# GiGaMega_sield_2.net
KiCad netlist of a schematic drawn in EAGLE
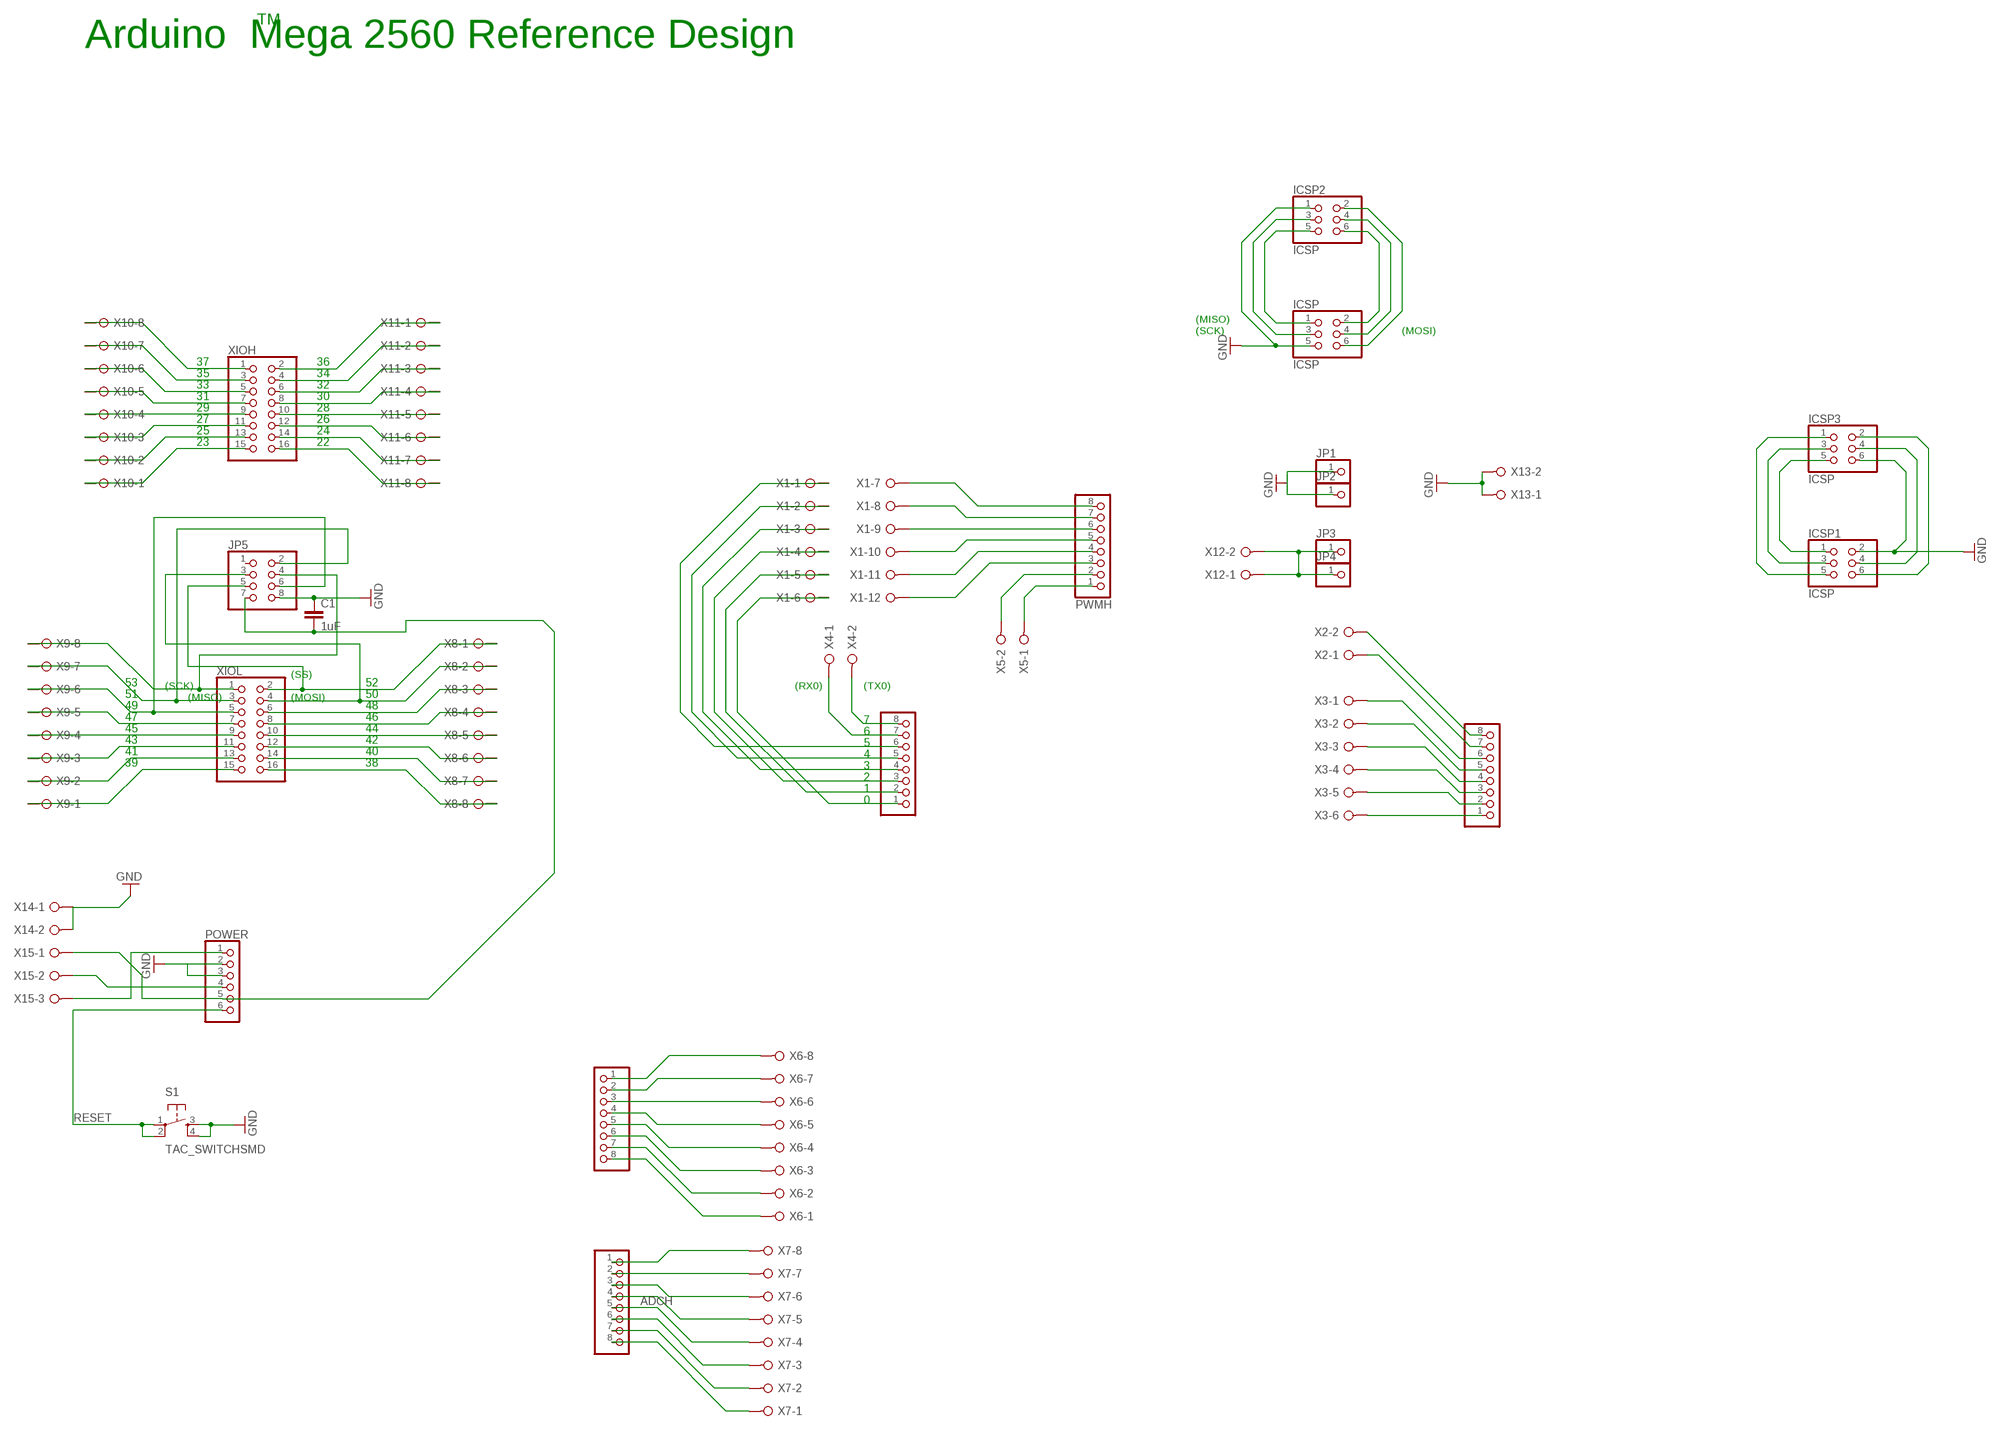
[diagram p0: schematic, sheet 1]

(export (version "E")
  (design (tool "Eeschema 10.0.6"))
  (components
    (comp (ref "ADCH")
      (value "PINHD-1X8")
      (footprint "eagle-import:1X08")
      (libsource (lib "eagle-import") (part "PINHD-1X8"))
    )
    (comp (ref "ADCL")
      (value "PINHD-1X8")
      (footprint "eagle-import:1X08")
      (libsource (lib "eagle-import") (part "PINHD-1X8"))
    )
    (comp (ref "C1")
      (value "1uF")
      (footprint "eagle-import:1206")
      (libsource (lib "eagle-import") (part "2.2UF-CERCAP-10009"))
    )
    (comp (ref "COMMUNICATION")
      (value "PINHD-1X8")
      (footprint "eagle-import:1X08")
      (libsource (lib "eagle-import") (part "PINHD-1X8"))
    )
    (comp (ref "ICSP")
      (value "ICSP")
      (footprint "eagle-import:2X03")
      (libsource (lib "eagle-import") (part "PINHD-2X3"))
    )
    (comp (ref "ICSP1")
      (value "ICSP")
      (footprint "eagle-import:2X03")
      (libsource (lib "eagle-import") (part "PINHD-2X3"))
    )
    (comp (ref "ICSP2")
      (value "ICSP")
      (footprint "eagle-import:2X03")
      (libsource (lib "eagle-import") (part "PINHD-2X3"))
    )
    (comp (ref "ICSP3")
      (value "ICSP")
      (footprint "eagle-import:2X03")
      (libsource (lib "eagle-import") (part "PINHD-2X3"))
    )
    (comp (ref "JP1")
      (value "PINHD-1X1")
      (footprint "eagle-import:1X01")
      (libsource (lib "eagle-import") (part "PINHD-1X1"))
    )
    (comp (ref "JP2")
      (value "PINHD-1X1")
      (footprint "eagle-import:1X01")
      (libsource (lib "eagle-import") (part "PINHD-1X1"))
    )
    (comp (ref "JP3")
      (value "PINHD-1X1")
      (footprint "eagle-import:1X01")
      (libsource (lib "eagle-import") (part "PINHD-1X1"))
    )
    (comp (ref "JP4")
      (value "PINHD-1X1")
      (footprint "eagle-import:1X01")
      (libsource (lib "eagle-import") (part "PINHD-1X1"))
    )
    (comp (ref "JP5")
      (value "PINHD-2X4")
      (footprint "eagle-import:2X04")
      (libsource (lib "eagle-import") (part "PINHD-2X4"))
    )
    (comp (ref "POWER")
      (value "PINHD-1X6")
      (footprint "eagle-import:1X06")
      (libsource (lib "eagle-import") (part "PINHD-1X6"))
    )
    (comp (ref "PWMH")
      (value "PINHD-1X8")
      (footprint "eagle-import:1X08")
      (libsource (lib "eagle-import") (part "PINHD-1X8"))
    )
    (comp (ref "PWML")
      (value "PINHD-1X8")
      (footprint "eagle-import:1X08")
      (libsource (lib "eagle-import") (part "PINHD-1X8"))
    )
    (comp (ref "S1")
      (value "TAC_SWITCHSMD")
      (footprint "eagle-import:TACTILE-SWITCH-SMD")
      (libsource (lib "eagle-import") (part "TAC_SWITCHSMD"))
    )
    (comp (ref "X1")
      (value "W237-12P")
      (footprint "eagle-import:W237-12P")
      (libsource (lib "eagle-import") (part "W237-12P"))
    )
    (comp (ref "X2")
      (value "W237-02P")
      (footprint "eagle-import:W237-132")
      (libsource (lib "eagle-import") (part "W237-02P"))
    )
    (comp (ref "X3")
      (value "W237-06P")
      (footprint "eagle-import:W237-6P")
      (libsource (lib "eagle-import") (part "W237-06P"))
    )
    (comp (ref "X4")
      (value "W237-02P")
      (footprint "eagle-import:W237-132")
      (libsource (lib "eagle-import") (part "W237-02P"))
    )
    (comp (ref "X5")
      (value "W237-02P")
      (footprint "eagle-import:W237-132")
      (libsource (lib "eagle-import") (part "W237-02P"))
    )
    (comp (ref "X6")
      (value "W237-08P")
      (footprint "eagle-import:W237-8P")
      (libsource (lib "eagle-import") (part "W237-08P"))
    )
    (comp (ref "X7")
      (value "W237-08P")
      (footprint "eagle-import:W237-8P")
      (libsource (lib "eagle-import") (part "W237-08P"))
    )
    (comp (ref "X8")
      (value "W237-08P")
      (footprint "eagle-import:W237-8P")
      (libsource (lib "eagle-import") (part "W237-08P"))
    )
    (comp (ref "X9")
      (value "W237-08P")
      (footprint "eagle-import:W237-8P")
      (libsource (lib "eagle-import") (part "W237-08P"))
    )
    (comp (ref "X10")
      (value "W237-08P")
      (footprint "eagle-import:W237-8P")
      (libsource (lib "eagle-import") (part "W237-08P"))
    )
    (comp (ref "X11")
      (value "W237-08P")
      (footprint "eagle-import:W237-8P")
      (libsource (lib "eagle-import") (part "W237-08P"))
    )
    (comp (ref "X12")
      (value "W237-02P")
      (footprint "eagle-import:W237-132")
      (libsource (lib "eagle-import") (part "W237-02P"))
    )
    (comp (ref "X13")
      (value "W237-02P")
      (footprint "eagle-import:W237-132")
      (libsource (lib "eagle-import") (part "W237-02P"))
    )
    (comp (ref "X14")
      (value "W237-02P")
      (footprint "eagle-import:W237-132")
      (libsource (lib "eagle-import") (part "W237-02P"))
    )
    (comp (ref "X15")
      (value "W237-03P")
      (footprint "eagle-import:W237-133")
      (libsource (lib "eagle-import") (part "W237-03P"))
    )
    (comp (ref "XIOH")
      (value "PINHD-2X8")
      (footprint "eagle-import:2X08")
      (libsource (lib "eagle-import") (part "PINHD-2X8"))
    )
    (comp (ref "XIOL")
      (value "PINHD-2X8")
      (footprint "eagle-import:2X08")
      (libsource (lib "eagle-import") (part "PINHD-2X8"))
    )
  )
  (nets
    (net (code "1") (name "/RESET") (class "Default")
      (node (ref "POWER") (pin "6") (pinfunction "6_6") (pintype "passive"))
      (node (ref "S1") (pin "1") (pinfunction "1_1") (pintype "passive"))
      (node (ref "S1") (pin "2") (pinfunction "2_2") (pintype "passive"))
    )
    (net (code "2") (name "GND") (class "Default")
      (node (ref "C1") (pin "1") (pinfunction "1_1") (pintype "passive"))
      (node (ref "ICSP") (pin "5") (pinfunction "5_5") (pintype "passive"))
      (node (ref "ICSP1") (pin "2") (pinfunction "2_2") (pintype "passive"))
      (node (ref "ICSP2") (pin "1") (pinfunction "1_1") (pintype "passive"))
      (node (ref "ICSP3") (pin "6") (pinfunction "6_6") (pintype "passive"))
      (node (ref "JP1") (pin "1") (pinfunction "1_1") (pintype "passive"))
      (node (ref "JP2") (pin "1") (pinfunction "1_1") (pintype "passive"))
      (node (ref "JP5") (pin "8") (pinfunction "8_8") (pintype "passive"))
      (node (ref "POWER") (pin "2") (pinfunction "2_2") (pintype "passive"))
      (node (ref "POWER") (pin "3") (pinfunction "3_3") (pintype "passive"))
      (node (ref "S1") (pin "3") (pinfunction "3_3") (pintype "passive"))
      (node (ref "S1") (pin "4") (pinfunction "4_4") (pintype "passive"))
      (node (ref "X13") (pin "1") (pinfunction "KL_1") (pintype "passive"))
      (node (ref "X13") (pin "2") (pinfunction "KL_2") (pintype "passive"))
      (node (ref "X14") (pin "1") (pinfunction "KL_1") (pintype "passive"))
      (node (ref "X14") (pin "2") (pinfunction "KL_2") (pintype "passive"))
    )
    (net (code "3") (name "Net-(ICSP-Pad1)") (class "Default")
      (node (ref "ICSP") (pin "1") (pinfunction "1_1") (pintype "passive"))
      (node (ref "ICSP2") (pin "5") (pinfunction "5_5") (pintype "passive"))
    )
    (net (code "4") (name "Net-(ICSP-Pad2)") (class "Default")
      (node (ref "ICSP") (pin "2") (pinfunction "2_2") (pintype "passive"))
      (node (ref "ICSP2") (pin "6") (pinfunction "6_6") (pintype "passive"))
    )
    (net (code "5") (name "Net-(ICSP-Pad3)") (class "Default")
      (node (ref "ICSP") (pin "3") (pinfunction "3_3") (pintype "passive"))
      (node (ref "ICSP2") (pin "3") (pinfunction "3_3") (pintype "passive"))
    )
    (net (code "6") (name "Net-(ICSP-Pad4)") (class "Default")
      (node (ref "ICSP") (pin "4") (pinfunction "4_4") (pintype "passive"))
      (node (ref "ICSP2") (pin "4") (pinfunction "4_4") (pintype "passive"))
    )
    (net (code "7") (name "Net-(ICSP-Pad6)") (class "Default")
      (node (ref "ICSP") (pin "6") (pinfunction "6_6") (pintype "passive"))
      (node (ref "ICSP2") (pin "2") (pinfunction "2_2") (pintype "passive"))
    )
    (net (code "8") (name "Net-(ICSP1-Pad1)") (class "Default")
      (node (ref "ICSP1") (pin "1") (pinfunction "1_1") (pintype "passive"))
      (node (ref "ICSP3") (pin "5") (pinfunction "5_5") (pintype "passive"))
    )
    (net (code "9") (name "Net-(ICSP1-Pad3)") (class "Default")
      (node (ref "ICSP1") (pin "3") (pinfunction "3_3") (pintype "passive"))
      (node (ref "ICSP3") (pin "3") (pinfunction "3_3") (pintype "passive"))
    )
    (net (code "10") (name "Net-(ICSP1-Pad4)") (class "Default")
      (node (ref "ICSP1") (pin "4") (pinfunction "4_4") (pintype "passive"))
      (node (ref "ICSP3") (pin "4") (pinfunction "4_4") (pintype "passive"))
    )
    (net (code "11") (name "Net-(ICSP1-Pad5)") (class "Default")
      (node (ref "ICSP1") (pin "5") (pinfunction "5_5") (pintype "passive"))
      (node (ref "ICSP3") (pin "1") (pinfunction "1_1") (pintype "passive"))
    )
    (net (code "12") (name "Net-(ICSP1-Pad6)") (class "Default")
      (node (ref "ICSP1") (pin "6") (pinfunction "6_6") (pintype "passive"))
      (node (ref "ICSP3") (pin "2") (pinfunction "2_2") (pintype "passive"))
    )
    (net (code "13") (name "Net-(X1A-KL)") (class "Default")
      (node (ref "PWML") (pin "6") (pinfunction "6_6") (pintype "passive"))
      (node (ref "X1") (pin "1") (pinfunction "KL_1") (pintype "passive"))
    )
    (net (code "14") (name "Net-(X1B-KL)") (class "Default")
      (node (ref "PWMH") (pin "5") (pinfunction "5_5") (pintype "passive"))
      (node (ref "X1") (pin "10") (pinfunction "KL_10") (pintype "passive"))
    )
    (net (code "15") (name "Net-(X1C-KL)") (class "Default")
      (node (ref "PWMH") (pin "4") (pinfunction "4_4") (pintype "passive"))
      (node (ref "X1") (pin "11") (pinfunction "KL_11") (pintype "passive"))
    )
    (net (code "16") (name "Net-(X1D-KL)") (class "Default")
      (node (ref "PWMH") (pin "3") (pinfunction "3_3") (pintype "passive"))
      (node (ref "X1") (pin "12") (pinfunction "KL_12") (pintype "passive"))
    )
    (net (code "17") (name "Net-(X1E-KL)") (class "Default")
      (node (ref "PWML") (pin "5") (pinfunction "5_5") (pintype "passive"))
      (node (ref "X1") (pin "2") (pinfunction "KL_2") (pintype "passive"))
    )
    (net (code "18") (name "Net-(X1F-KL)") (class "Default")
      (node (ref "PWML") (pin "4") (pinfunction "4_4") (pintype "passive"))
      (node (ref "X1") (pin "3") (pinfunction "KL_3") (pintype "passive"))
    )
    (net (code "19") (name "Net-(X1G-KL)") (class "Default")
      (node (ref "PWML") (pin "3") (pinfunction "3_3") (pintype "passive"))
      (node (ref "X1") (pin "4") (pinfunction "KL_4") (pintype "passive"))
    )
    (net (code "20") (name "Net-(X1H-KL)") (class "Default")
      (node (ref "PWML") (pin "2") (pinfunction "2_2") (pintype "passive"))
      (node (ref "X1") (pin "5") (pinfunction "KL_5") (pintype "passive"))
    )
    (net (code "21") (name "Net-(X1I-KL)") (class "Default")
      (node (ref "PWML") (pin "1") (pinfunction "1_1") (pintype "passive"))
      (node (ref "X1") (pin "6") (pinfunction "KL_6") (pintype "passive"))
    )
    (net (code "22") (name "Net-(X1J-KL)") (class "Default")
      (node (ref "PWMH") (pin "8") (pinfunction "8_8") (pintype "passive"))
      (node (ref "X1") (pin "7") (pinfunction "KL_7") (pintype "passive"))
    )
    (net (code "23") (name "Net-(X1K-KL)") (class "Default")
      (node (ref "PWMH") (pin "7") (pinfunction "7_7") (pintype "passive"))
      (node (ref "X1") (pin "8") (pinfunction "KL_8") (pintype "passive"))
    )
    (net (code "24") (name "Net-(X1L-KL)") (class "Default")
      (node (ref "PWMH") (pin "6") (pinfunction "6_6") (pintype "passive"))
      (node (ref "X1") (pin "9") (pinfunction "KL_9") (pintype "passive"))
    )
    (net (code "25") (name "Net-(X2A-KL)") (class "Default")
      (node (ref "COMMUNICATION") (pin "7") (pinfunction "7_7") (pintype "passive"))
      (node (ref "X2") (pin "1") (pinfunction "KL_1") (pintype "passive"))
    )
    (net (code "26") (name "Net-(X2B-KL)") (class "Default")
      (node (ref "COMMUNICATION") (pin "8") (pinfunction "8_8") (pintype "passive"))
      (node (ref "X2") (pin "2") (pinfunction "KL_2") (pintype "passive"))
    )
    (net (code "27") (name "Net-(X3A-KL)") (class "Default")
      (node (ref "COMMUNICATION") (pin "6") (pinfunction "6_6") (pintype "passive"))
      (node (ref "X3") (pin "1") (pinfunction "KL_1") (pintype "passive"))
    )
    (net (code "28") (name "Net-(X3B-KL)") (class "Default")
      (node (ref "COMMUNICATION") (pin "5") (pinfunction "5_5") (pintype "passive"))
      (node (ref "X3") (pin "2") (pinfunction "KL_2") (pintype "passive"))
    )
    (net (code "29") (name "Net-(X3C-KL)") (class "Default")
      (node (ref "COMMUNICATION") (pin "4") (pinfunction "4_4") (pintype "passive"))
      (node (ref "X3") (pin "3") (pinfunction "KL_3") (pintype "passive"))
    )
    (net (code "30") (name "Net-(X3D-KL)") (class "Default")
      (node (ref "COMMUNICATION") (pin "3") (pinfunction "3_3") (pintype "passive"))
      (node (ref "X3") (pin "4") (pinfunction "KL_4") (pintype "passive"))
    )
    (net (code "31") (name "Net-(X3E-KL)") (class "Default")
      (node (ref "COMMUNICATION") (pin "2") (pinfunction "2_2") (pintype "passive"))
      (node (ref "X3") (pin "5") (pinfunction "KL_5") (pintype "passive"))
    )
    (net (code "32") (name "Net-(X3F-KL)") (class "Default")
      (node (ref "COMMUNICATION") (pin "1") (pinfunction "1_1") (pintype "passive"))
      (node (ref "X3") (pin "6") (pinfunction "KL_6") (pintype "passive"))
    )
    (net (code "33") (name "Net-(X4A-KL)") (class "Default")
      (node (ref "PWML") (pin "7") (pinfunction "7_7") (pintype "passive"))
      (node (ref "X4") (pin "1") (pinfunction "KL_1") (pintype "passive"))
    )
    (net (code "34") (name "Net-(X4B-KL)") (class "Default")
      (node (ref "PWML") (pin "8") (pinfunction "8_8") (pintype "passive"))
      (node (ref "X4") (pin "2") (pinfunction "KL_2") (pintype "passive"))
    )
    (net (code "35") (name "Net-(X5A-KL)") (class "Default")
      (node (ref "PWMH") (pin "1") (pinfunction "1_1") (pintype "passive"))
      (node (ref "X5") (pin "1") (pinfunction "KL_1") (pintype "passive"))
    )
    (net (code "36") (name "Net-(X5B-KL)") (class "Default")
      (node (ref "PWMH") (pin "2") (pinfunction "2_2") (pintype "passive"))
      (node (ref "X5") (pin "2") (pinfunction "KL_2") (pintype "passive"))
    )
    (net (code "37") (name "Net-(X6A-KL)") (class "Default")
      (node (ref "ADCL") (pin "8") (pinfunction "8_8") (pintype "passive"))
      (node (ref "X6") (pin "1") (pinfunction "KL_1") (pintype "passive"))
    )
    (net (code "38") (name "Net-(X6B-KL)") (class "Default")
      (node (ref "ADCL") (pin "7") (pinfunction "7_7") (pintype "passive"))
      (node (ref "X6") (pin "2") (pinfunction "KL_2") (pintype "passive"))
    )
    (net (code "39") (name "Net-(X6C-KL)") (class "Default")
      (node (ref "ADCL") (pin "6") (pinfunction "6_6") (pintype "passive"))
      (node (ref "X6") (pin "3") (pinfunction "KL_3") (pintype "passive"))
    )
    (net (code "40") (name "Net-(X6D-KL)") (class "Default")
      (node (ref "ADCL") (pin "5") (pinfunction "5_5") (pintype "passive"))
      (node (ref "X6") (pin "4") (pinfunction "KL_4") (pintype "passive"))
    )
    (net (code "41") (name "Net-(X6E-KL)") (class "Default")
      (node (ref "ADCL") (pin "4") (pinfunction "4_4") (pintype "passive"))
      (node (ref "X6") (pin "5") (pinfunction "KL_5") (pintype "passive"))
    )
    (net (code "42") (name "Net-(X6F-KL)") (class "Default")
      (node (ref "ADCL") (pin "3") (pinfunction "3_3") (pintype "passive"))
      (node (ref "X6") (pin "6") (pinfunction "KL_6") (pintype "passive"))
    )
    (net (code "43") (name "Net-(X6G-KL)") (class "Default")
      (node (ref "ADCL") (pin "2") (pinfunction "2_2") (pintype "passive"))
      (node (ref "X6") (pin "7") (pinfunction "KL_7") (pintype "passive"))
    )
    (net (code "44") (name "Net-(X6H-KL)") (class "Default")
      (node (ref "ADCL") (pin "1") (pinfunction "1_1") (pintype "passive"))
      (node (ref "X6") (pin "8") (pinfunction "KL_8") (pintype "passive"))
    )
    (net (code "45") (name "Net-(X7A-KL)") (class "Default")
      (node (ref "ADCH") (pin "8") (pinfunction "8_8") (pintype "passive"))
      (node (ref "X7") (pin "1") (pinfunction "KL_1") (pintype "passive"))
    )
    (net (code "46") (name "Net-(X7B-KL)") (class "Default")
      (node (ref "ADCH") (pin "7") (pinfunction "7_7") (pintype "passive"))
      (node (ref "X7") (pin "2") (pinfunction "KL_2") (pintype "passive"))
    )
    (net (code "47") (name "Net-(X7C-KL)") (class "Default")
      (node (ref "ADCH") (pin "6") (pinfunction "6_6") (pintype "passive"))
      (node (ref "X7") (pin "3") (pinfunction "KL_3") (pintype "passive"))
    )
    (net (code "48") (name "Net-(X7D-KL)") (class "Default")
      (node (ref "ADCH") (pin "5") (pinfunction "5_5") (pintype "passive"))
      (node (ref "X7") (pin "4") (pinfunction "KL_4") (pintype "passive"))
    )
    (net (code "49") (name "Net-(X7E-KL)") (class "Default")
      (node (ref "ADCH") (pin "4") (pinfunction "4_4") (pintype "passive"))
      (node (ref "X7") (pin "5") (pinfunction "KL_5") (pintype "passive"))
    )
    (net (code "50") (name "Net-(X7F-KL)") (class "Default")
      (node (ref "ADCH") (pin "3") (pinfunction "3_3") (pintype "passive"))
      (node (ref "X7") (pin "6") (pinfunction "KL_6") (pintype "passive"))
    )
    (net (code "51") (name "Net-(X7G-KL)") (class "Default")
      (node (ref "ADCH") (pin "2") (pinfunction "2_2") (pintype "passive"))
      (node (ref "X7") (pin "7") (pinfunction "KL_7") (pintype "passive"))
    )
    (net (code "52") (name "Net-(X7H-KL)") (class "Default")
      (node (ref "ADCH") (pin "1") (pinfunction "1_1") (pintype "passive"))
      (node (ref "X7") (pin "8") (pinfunction "KL_8") (pintype "passive"))
    )
    (net (code "53") (name "Net-(X8A-KL)") (class "Default")
      (node (ref "JP5") (pin "5") (pinfunction "5_5") (pintype "passive"))
      (node (ref "X8") (pin "1") (pinfunction "KL_1") (pintype "passive"))
      (node (ref "XIOL") (pin "2") (pinfunction "2_2") (pintype "passive"))
    )
    (net (code "54") (name "Net-(X8B-KL)") (class "Default")
      (node (ref "JP5") (pin "3") (pinfunction "3_3") (pintype "passive"))
      (node (ref "X8") (pin "2") (pinfunction "KL_2") (pintype "passive"))
      (node (ref "XIOL") (pin "4") (pinfunction "4_4") (pintype "passive"))
    )
    (net (code "55") (name "Net-(X8C-KL)") (class "Default")
      (node (ref "X8") (pin "3") (pinfunction "KL_3") (pintype "passive"))
      (node (ref "XIOL") (pin "6") (pinfunction "6_6") (pintype "passive"))
    )
    (net (code "56") (name "Net-(X8D-KL)") (class "Default")
      (node (ref "X8") (pin "4") (pinfunction "KL_4") (pintype "passive"))
      (node (ref "XIOL") (pin "8") (pinfunction "8_8") (pintype "passive"))
    )
    (net (code "57") (name "Net-(X8E-KL)") (class "Default")
      (node (ref "X8") (pin "5") (pinfunction "KL_5") (pintype "passive"))
      (node (ref "XIOL") (pin "10") (pinfunction "10_10") (pintype "passive"))
    )
    (net (code "58") (name "Net-(X8F-KL)") (class "Default")
      (node (ref "X8") (pin "6") (pinfunction "KL_6") (pintype "passive"))
      (node (ref "XIOL") (pin "12") (pinfunction "12_12") (pintype "passive"))
    )
    (net (code "59") (name "Net-(X8G-KL)") (class "Default")
      (node (ref "X8") (pin "7") (pinfunction "KL_7") (pintype "passive"))
      (node (ref "XIOL") (pin "14") (pinfunction "14_14") (pintype "passive"))
    )
    (net (code "60") (name "Net-(X8H-KL)") (class "Default")
      (node (ref "X8") (pin "8") (pinfunction "KL_8") (pintype "passive"))
      (node (ref "XIOL") (pin "16") (pinfunction "16_16") (pintype "passive"))
    )
    (net (code "61") (name "Net-(X9A-KL)") (class "Default")
      (node (ref "X9") (pin "1") (pinfunction "KL_1") (pintype "passive"))
      (node (ref "XIOL") (pin "15") (pinfunction "15_15") (pintype "passive"))
    )
    (net (code "62") (name "Net-(X9B-KL)") (class "Default")
      (node (ref "X9") (pin "2") (pinfunction "KL_2") (pintype "passive"))
      (node (ref "XIOL") (pin "13") (pinfunction "13_13") (pintype "passive"))
    )
    (net (code "63") (name "Net-(X9C-KL)") (class "Default")
      (node (ref "X9") (pin "3") (pinfunction "KL_3") (pintype "passive"))
      (node (ref "XIOL") (pin "11") (pinfunction "11_11") (pintype "passive"))
    )
    (net (code "64") (name "Net-(X9D-KL)") (class "Default")
      (node (ref "X9") (pin "4") (pinfunction "KL_4") (pintype "passive"))
      (node (ref "XIOL") (pin "9") (pinfunction "9_9") (pintype "passive"))
    )
    (net (code "65") (name "Net-(X9E-KL)") (class "Default")
      (node (ref "X9") (pin "5") (pinfunction "KL_5") (pintype "passive"))
      (node (ref "XIOL") (pin "7") (pinfunction "7_7") (pintype "passive"))
    )
    (net (code "66") (name "Net-(X9F-KL)") (class "Default")
      (node (ref "JP5") (pin "6") (pinfunction "6_6") (pintype "passive"))
      (node (ref "X9") (pin "6") (pinfunction "KL_6") (pintype "passive"))
      (node (ref "XIOL") (pin "5") (pinfunction "5_5") (pintype "passive"))
    )
    (net (code "67") (name "Net-(X9G-KL)") (class "Default")
      (node (ref "JP5") (pin "2") (pinfunction "2_2") (pintype "passive"))
      (node (ref "X9") (pin "7") (pinfunction "KL_7") (pintype "passive"))
      (node (ref "XIOL") (pin "3") (pinfunction "3_3") (pintype "passive"))
    )
    (net (code "68") (name "Net-(X9H-KL)") (class "Default")
      (node (ref "JP5") (pin "4") (pinfunction "4_4") (pintype "passive"))
      (node (ref "X9") (pin "8") (pinfunction "KL_8") (pintype "passive"))
      (node (ref "XIOL") (pin "1") (pinfunction "1_1") (pintype "passive"))
    )
    (net (code "69") (name "Net-(X10A-KL)") (class "Default")
      (node (ref "X10") (pin "1") (pinfunction "KL_1") (pintype "passive"))
      (node (ref "XIOH") (pin "15") (pinfunction "15_15") (pintype "passive"))
    )
    (net (code "70") (name "Net-(X10B-KL)") (class "Default")
      (node (ref "X10") (pin "2") (pinfunction "KL_2") (pintype "passive"))
      (node (ref "XIOH") (pin "13") (pinfunction "13_13") (pintype "passive"))
    )
    (net (code "71") (name "Net-(X10C-KL)") (class "Default")
      (node (ref "X10") (pin "3") (pinfunction "KL_3") (pintype "passive"))
      (node (ref "XIOH") (pin "11") (pinfunction "11_11") (pintype "passive"))
    )
    (net (code "72") (name "Net-(X10D-KL)") (class "Default")
      (node (ref "X10") (pin "4") (pinfunction "KL_4") (pintype "passive"))
      (node (ref "XIOH") (pin "9") (pinfunction "9_9") (pintype "passive"))
    )
    (net (code "73") (name "Net-(X10E-KL)") (class "Default")
      (node (ref "X10") (pin "5") (pinfunction "KL_5") (pintype "passive"))
      (node (ref "XIOH") (pin "7") (pinfunction "7_7") (pintype "passive"))
    )
    (net (code "74") (name "Net-(X10F-KL)") (class "Default")
      (node (ref "X10") (pin "6") (pinfunction "KL_6") (pintype "passive"))
      (node (ref "XIOH") (pin "5") (pinfunction "5_5") (pintype "passive"))
    )
    (net (code "75") (name "Net-(X10G-KL)") (class "Default")
      (node (ref "X10") (pin "7") (pinfunction "KL_7") (pintype "passive"))
      (node (ref "XIOH") (pin "3") (pinfunction "3_3") (pintype "passive"))
    )
    (net (code "76") (name "Net-(X10H-KL)") (class "Default")
      (node (ref "X10") (pin "8") (pinfunction "KL_8") (pintype "passive"))
      (node (ref "XIOH") (pin "1") (pinfunction "1_1") (pintype "passive"))
    )
    (net (code "77") (name "Net-(X11A-KL)") (class "Default")
      (node (ref "X11") (pin "1") (pinfunction "KL_1") (pintype "passive"))
      (node (ref "XIOH") (pin "2") (pinfunction "2_2") (pintype "passive"))
    )
    (net (code "78") (name "Net-(X11B-KL)") (class "Default")
      (node (ref "X11") (pin "2") (pinfunction "KL_2") (pintype "passive"))
      (node (ref "XIOH") (pin "4") (pinfunction "4_4") (pintype "passive"))
    )
    (net (code "79") (name "Net-(X11C-KL)") (class "Default")
      (node (ref "X11") (pin "3") (pinfunction "KL_3") (pintype "passive"))
      (node (ref "XIOH") (pin "6") (pinfunction "6_6") (pintype "passive"))
    )
    (net (code "80") (name "Net-(X11D-KL)") (class "Default")
      (node (ref "X11") (pin "4") (pinfunction "KL_4") (pintype "passive"))
      (node (ref "XIOH") (pin "8") (pinfunction "8_8") (pintype "passive"))
    )
    (net (code "81") (name "Net-(X11E-KL)") (class "Default")
      (node (ref "X11") (pin "5") (pinfunction "KL_5") (pintype "passive"))
      (node (ref "XIOH") (pin "10") (pinfunction "10_10") (pintype "passive"))
    )
    (net (code "82") (name "Net-(X11F-KL)") (class "Default")
      (node (ref "X11") (pin "6") (pinfunction "KL_6") (pintype "passive"))
      (node (ref "XIOH") (pin "12") (pinfunction "12_12") (pintype "passive"))
    )
    (net (code "83") (name "Net-(X11G-KL)") (class "Default")
      (node (ref "X11") (pin "7") (pinfunction "KL_7") (pintype "passive"))
      (node (ref "XIOH") (pin "14") (pinfunction "14_14") (pintype "passive"))
    )
    (net (code "84") (name "Net-(X11H-KL)") (class "Default")
      (node (ref "X11") (pin "8") (pinfunction "KL_8") (pintype "passive"))
      (node (ref "XIOH") (pin "16") (pinfunction "16_16") (pintype "passive"))
    )
    (net (code "85") (name "Net-(X12A-KL)") (class "Default")
      (node (ref "JP3") (pin "1") (pinfunction "1_1") (pintype "passive"))
      (node (ref "JP4") (pin "1") (pinfunction "1_1") (pintype "passive"))
      (node (ref "X12") (pin "1") (pinfunction "KL_1") (pintype "passive"))
      (node (ref "X12") (pin "2") (pinfunction "KL_2") (pintype "passive"))
    )
    (net (code "86") (name "Net-(X15A-KL)") (class "Default")
      (node (ref "C1") (pin "2") (pinfunction "2_2") (pintype "passive"))
      (node (ref "JP5") (pin "7") (pinfunction "7_7") (pintype "passive"))
      (node (ref "POWER") (pin "5") (pinfunction "5_5") (pintype "passive"))
      (node (ref "X15") (pin "1") (pinfunction "KL_1") (pintype "passive"))
    )
    (net (code "87") (name "Net-(X15B-KL)") (class "Default")
      (node (ref "POWER") (pin "4") (pinfunction "4_4") (pintype "passive"))
      (node (ref "X15") (pin "2") (pinfunction "KL_2") (pintype "passive"))
    )
    (net (code "88") (name "Net-(X15C-KL)") (class "Default")
      (node (ref "POWER") (pin "1") (pinfunction "1_1") (pintype "passive"))
      (node (ref "X15") (pin "3") (pinfunction "KL_3") (pintype "passive"))
    )
    (net (code "89") (name "unconnected-(JP5-Pad1)") (class "Default")
      (node (ref "JP5") (pin "1") (pinfunction "1_1") (pintype "passive"))
    )
  )
)
